# Sheet.net
KiCad netlist of a schematic drawn in Altium Designer
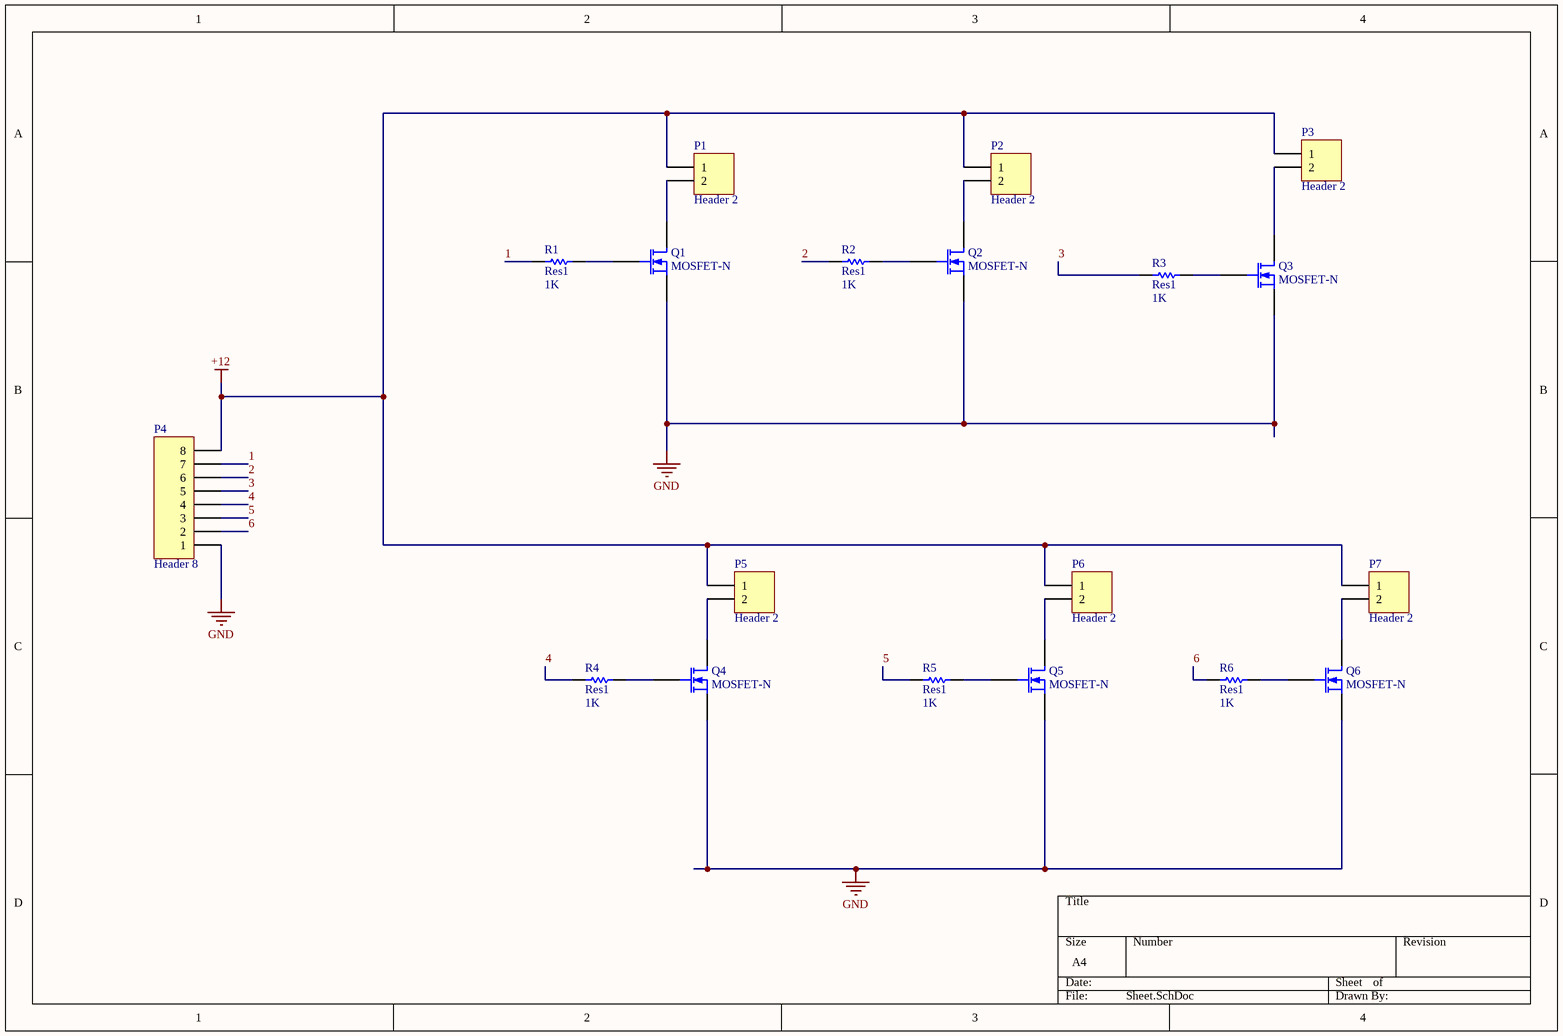
[diagram p0: Sheet.SchDoc]

(export (version "E")
  (design (tool "Eeschema 10.0.6"))
  (components
    (comp (ref "P1")
      (value "Header 2")
      (footprint "HDR1X2")
      (description "Header, 2-Pin")
      (fields (field (name "PUBLISHER") "Altium Limited"))
      (libsource (lib "Miscellaneous Connectors") (part "Header 2"))
    )
    (comp (ref "P2")
      (value "Header 2")
      (footprint "HDR1X2")
      (description "Header, 2-Pin")
      (fields (field (name "PUBLISHER") "Altium Limited"))
      (libsource (lib "Miscellaneous Connectors") (part "Header 2"))
    )
    (comp (ref "P3")
      (value "Header 2")
      (footprint "HDR1X2")
      (description "Header, 2-Pin")
      (fields (field (name "PUBLISHER") "Altium Limited"))
      (libsource (lib "Miscellaneous Connectors") (part "Header 2"))
    )
    (comp (ref "P4")
      (value "Header 8")
      (footprint "HDR1X8")
      (description "Header, 8-Pin")
      (fields (field (name "PUBLISHER") "Altium Limited"))
      (libsource (lib "Miscellaneous Connectors") (part "Header 8"))
    )
    (comp (ref "P5")
      (value "Header 2")
      (footprint "HDR1X2")
      (description "Header, 2-Pin")
      (fields (field (name "PUBLISHER") "Altium Limited"))
      (libsource (lib "Miscellaneous Connectors") (part "Header 2"))
    )
    (comp (ref "P6")
      (value "Header 2")
      (footprint "HDR1X2")
      (description "Header, 2-Pin")
      (fields (field (name "PUBLISHER") "Altium Limited"))
      (libsource (lib "Miscellaneous Connectors") (part "Header 2"))
    )
    (comp (ref "P7")
      (value "Header 2")
      (footprint "HDR1X2")
      (description "Header, 2-Pin")
      (fields (field (name "PUBLISHER") "Altium Limited"))
      (libsource (lib "Miscellaneous Connectors") (part "Header 2"))
    )
    (comp (ref "Q1")
      (value "MOSFET-N")
      (footprint "E3")
      (description "N-Channel MOSFET")
      (fields (field (name "PUBLISHER") "Altium Limited"))
      (libsource (lib "Miscellaneous Devices") (part "MOSFET-N"))
    )
    (comp (ref "Q2")
      (value "MOSFET-N")
      (footprint "E3")
      (description "N-Channel MOSFET")
      (fields (field (name "PUBLISHER") "Altium Limited"))
      (libsource (lib "Miscellaneous Devices") (part "MOSFET-N"))
    )
    (comp (ref "Q3")
      (value "MOSFET-N")
      (footprint "E3")
      (description "N-Channel MOSFET")
      (fields (field (name "PUBLISHER") "Altium Limited"))
      (libsource (lib "Miscellaneous Devices") (part "MOSFET-N"))
    )
    (comp (ref "Q4")
      (value "MOSFET-N")
      (footprint "E3")
      (description "N-Channel MOSFET")
      (fields (field (name "PUBLISHER") "Altium Limited"))
      (libsource (lib "Miscellaneous Devices") (part "MOSFET-N"))
    )
    (comp (ref "Q5")
      (value "MOSFET-N")
      (footprint "E3")
      (description "N-Channel MOSFET")
      (fields (field (name "PUBLISHER") "Altium Limited"))
      (libsource (lib "Miscellaneous Devices") (part "MOSFET-N"))
    )
    (comp (ref "Q6")
      (value "MOSFET-N")
      (footprint "E3")
      (description "N-Channel MOSFET")
      (fields (field (name "PUBLISHER") "Altium Limited"))
      (libsource (lib "Miscellaneous Devices") (part "MOSFET-N"))
    )
    (comp (ref "R1")
      (value "Res1")
      (footprint "AXIAL-0.3")
      (description "Resistor")
      (fields (field (name "ALTIUM_VALUE") "1K") (field (name "PUBLISHER") "Altium Limited"))
      (libsource (lib "Miscellaneous Devices") (part "Res1"))
    )
    (comp (ref "R2")
      (value "Res1")
      (footprint "AXIAL-0.3")
      (description "Resistor")
      (fields (field (name "ALTIUM_VALUE") "1K") (field (name "PUBLISHER") "Altium Limited"))
      (libsource (lib "Miscellaneous Devices") (part "Res1"))
    )
    (comp (ref "R3")
      (value "Res1")
      (footprint "AXIAL-0.3")
      (description "Resistor")
      (fields (field (name "ALTIUM_VALUE") "1K") (field (name "PUBLISHER") "Altium Limited"))
      (libsource (lib "Miscellaneous Devices") (part "Res1"))
    )
    (comp (ref "R4")
      (value "Res1")
      (footprint "AXIAL-0.3")
      (description "Resistor")
      (fields (field (name "ALTIUM_VALUE") "1K") (field (name "PUBLISHER") "Altium Limited"))
      (libsource (lib "Miscellaneous Devices") (part "Res1"))
    )
    (comp (ref "R5")
      (value "Res1")
      (footprint "AXIAL-0.3")
      (description "Resistor")
      (fields (field (name "ALTIUM_VALUE") "1K") (field (name "PUBLISHER") "Altium Limited"))
      (libsource (lib "Miscellaneous Devices") (part "Res1"))
    )
    (comp (ref "R6")
      (value "Res1")
      (footprint "AXIAL-0.3")
      (description "Resistor")
      (fields (field (name "ALTIUM_VALUE") "1K") (field (name "PUBLISHER") "Altium Limited"))
      (libsource (lib "Miscellaneous Devices") (part "Res1"))
    )
  )
  (nets
    (net (code "1") (name "+12") (class "Default")
      (node (ref "P1") (pin "1") (pinfunction "1_1") (pintype "passive"))
      (node (ref "P2") (pin "1") (pinfunction "1_1") (pintype "passive"))
      (node (ref "P3") (pin "1") (pinfunction "1_1") (pintype "passive"))
      (node (ref "P4") (pin "8") (pinfunction "8_8") (pintype "passive"))
      (node (ref "P5") (pin "1") (pinfunction "1_1") (pintype "passive"))
      (node (ref "P6") (pin "1") (pinfunction "1_1") (pintype "passive"))
      (node (ref "P7") (pin "1") (pinfunction "1_1") (pintype "passive"))
    )
    (net (code "2") (name "/1") (class "Default")
      (node (ref "P4") (pin "7") (pinfunction "7_7") (pintype "passive"))
      (node (ref "R1") (pin "1") (pinfunction "1_1") (pintype "passive"))
    )
    (net (code "3") (name "/2") (class "Default")
      (node (ref "P4") (pin "6") (pinfunction "6_6") (pintype "passive"))
      (node (ref "R2") (pin "1") (pinfunction "1_1") (pintype "passive"))
    )
    (net (code "4") (name "/3") (class "Default")
      (node (ref "P4") (pin "5") (pinfunction "5_5") (pintype "passive"))
      (node (ref "R3") (pin "1") (pinfunction "1_1") (pintype "passive"))
    )
    (net (code "5") (name "/4") (class "Default")
      (node (ref "P4") (pin "4") (pinfunction "4_4") (pintype "passive"))
      (node (ref "R4") (pin "1") (pinfunction "1_1") (pintype "passive"))
    )
    (net (code "6") (name "/5") (class "Default")
      (node (ref "P4") (pin "3") (pinfunction "3_3") (pintype "passive"))
      (node (ref "R5") (pin "1") (pinfunction "1_1") (pintype "passive"))
    )
    (net (code "7") (name "/6") (class "Default")
      (node (ref "P4") (pin "2") (pinfunction "2_2") (pintype "passive"))
      (node (ref "R6") (pin "1") (pinfunction "1_1") (pintype "passive"))
    )
    (net (code "8") (name "GND") (class "Default")
      (node (ref "P4") (pin "1") (pinfunction "1_1") (pintype "passive"))
      (node (ref "Q1") (pin "3") (pinfunction "S_3") (pintype "passive"))
      (node (ref "Q2") (pin "3") (pinfunction "S_3") (pintype "passive"))
      (node (ref "Q3") (pin "3") (pinfunction "S_3") (pintype "passive"))
      (node (ref "Q4") (pin "3") (pinfunction "S_3") (pintype "passive"))
      (node (ref "Q5") (pin "3") (pinfunction "S_3") (pintype "passive"))
      (node (ref "Q6") (pin "3") (pinfunction "S_3") (pintype "passive"))
    )
    (net (code "9") (name "Net-(Q1-D)") (class "Default")
      (node (ref "P1") (pin "2") (pinfunction "2_2") (pintype "passive"))
      (node (ref "Q1") (pin "1") (pinfunction "D_1") (pintype "passive"))
    )
    (net (code "10") (name "Net-(Q1-G)") (class "Default")
      (node (ref "Q1") (pin "2") (pinfunction "G_2") (pintype "passive"))
      (node (ref "R1") (pin "2") (pinfunction "2_2") (pintype "passive"))
    )
    (net (code "11") (name "Net-(Q2-D)") (class "Default")
      (node (ref "P2") (pin "2") (pinfunction "2_2") (pintype "passive"))
      (node (ref "Q2") (pin "1") (pinfunction "D_1") (pintype "passive"))
    )
    (net (code "12") (name "Net-(Q2-G)") (class "Default")
      (node (ref "Q2") (pin "2") (pinfunction "G_2") (pintype "passive"))
      (node (ref "R2") (pin "2") (pinfunction "2_2") (pintype "passive"))
    )
    (net (code "13") (name "Net-(Q3-D)") (class "Default")
      (node (ref "P3") (pin "2") (pinfunction "2_2") (pintype "passive"))
      (node (ref "Q3") (pin "1") (pinfunction "D_1") (pintype "passive"))
    )
    (net (code "14") (name "Net-(Q3-G)") (class "Default")
      (node (ref "Q3") (pin "2") (pinfunction "G_2") (pintype "passive"))
      (node (ref "R3") (pin "2") (pinfunction "2_2") (pintype "passive"))
    )
    (net (code "15") (name "Net-(Q4-D)") (class "Default")
      (node (ref "P5") (pin "2") (pinfunction "2_2") (pintype "passive"))
      (node (ref "Q4") (pin "1") (pinfunction "D_1") (pintype "passive"))
    )
    (net (code "16") (name "Net-(Q4-G)") (class "Default")
      (node (ref "Q4") (pin "2") (pinfunction "G_2") (pintype "passive"))
      (node (ref "R4") (pin "2") (pinfunction "2_2") (pintype "passive"))
    )
    (net (code "17") (name "Net-(Q5-D)") (class "Default")
      (node (ref "P6") (pin "2") (pinfunction "2_2") (pintype "passive"))
      (node (ref "Q5") (pin "1") (pinfunction "D_1") (pintype "passive"))
    )
    (net (code "18") (name "Net-(Q5-G)") (class "Default")
      (node (ref "Q5") (pin "2") (pinfunction "G_2") (pintype "passive"))
      (node (ref "R5") (pin "2") (pinfunction "2_2") (pintype "passive"))
    )
    (net (code "19") (name "Net-(Q6-D)") (class "Default")
      (node (ref "P7") (pin "2") (pinfunction "2_2") (pintype "passive"))
      (node (ref "Q6") (pin "1") (pinfunction "D_1") (pintype "passive"))
    )
    (net (code "20") (name "Net-(Q6-G)") (class "Default")
      (node (ref "Q6") (pin "2") (pinfunction "G_2") (pintype "passive"))
      (node (ref "R6") (pin "2") (pinfunction "2_2") (pintype "passive"))
    )
  )
)
